# charger_v3.net
KiCad netlist of a schematic drawn in EAGLE
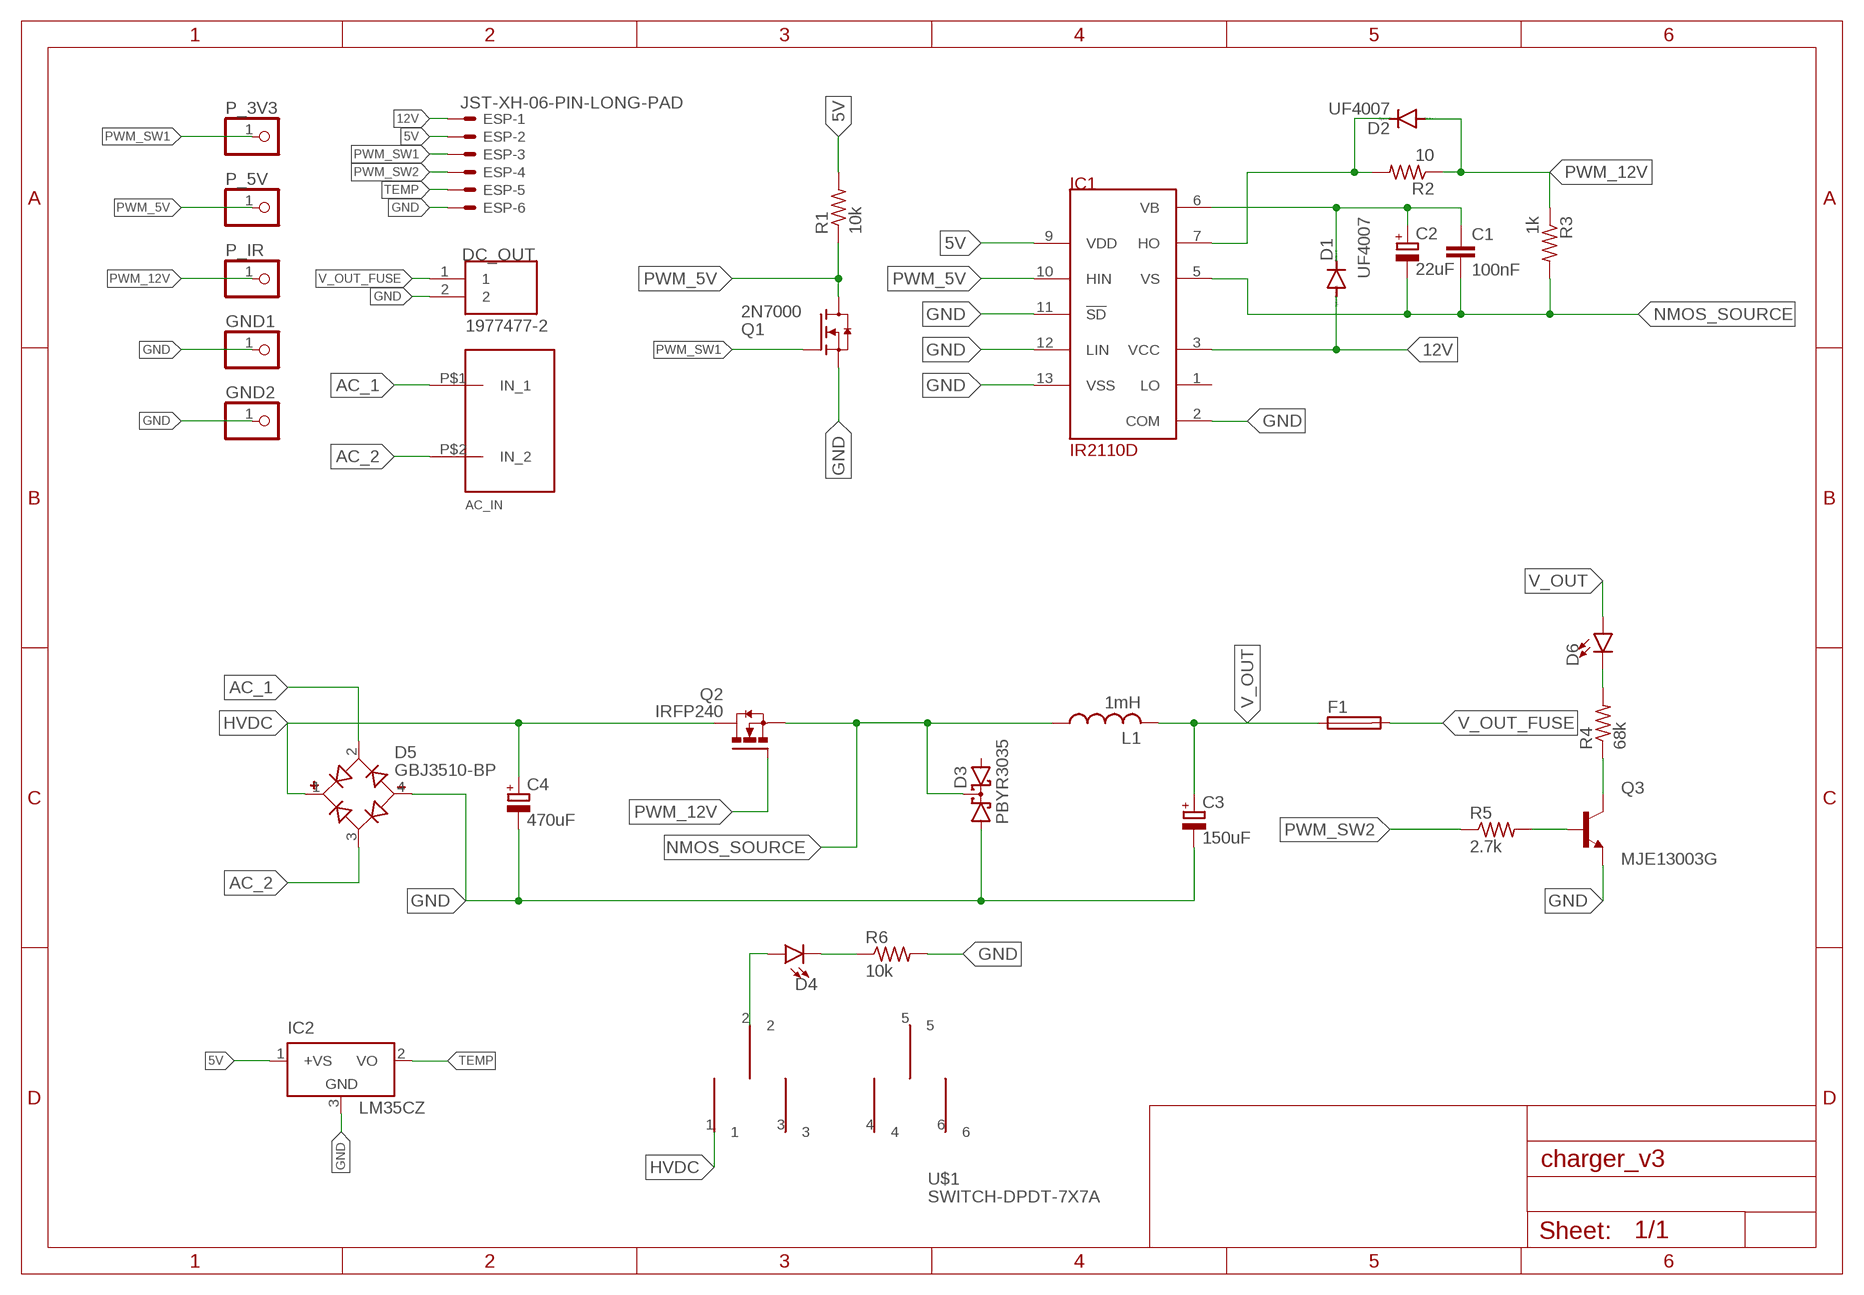
[diagram p0: schematic, sheet 1]

(export (version "E")
  (design (tool "Eeschema 10.0.6"))
  (components
    (comp (ref "AC_IN")
      (value "XT90A")
      (footprint "eagle-import:XT90-PAD")
      (libsource (lib "eagle-import") (part "XT90A"))
    )
    (comp (ref "C1")
      (value "100nF")
      (footprint "eagle-import:C025-025X050")
      (libsource (lib "eagle-import") (part "C-EU025-025X050"))
    )
    (comp (ref "C2")
      (value "22uF")
      (footprint "eagle-import:E2,5-6E")
      (libsource (lib "eagle-import") (part "CPOL-EUE2,5-6E"))
    )
    (comp (ref "C3")
      (value "150uF")
      (footprint "eagle-import:E7,5-18")
      (libsource (lib "eagle-import") (part "CPOL-EUE7.5-18"))
    )
    (comp (ref "C4")
      (value "470uF")
      (footprint "eagle-import:EB35D")
      (libsource (lib "eagle-import") (part "CPOL-EUE10-35"))
    )
    (comp (ref "D1")
      (value "UF4007")
      (footprint "eagle-import:DO34-7")
      (libsource (lib "eagle-import") (part "BAS15"))
    )
    (comp (ref "D2")
      (value "UF4007")
      (footprint "eagle-import:DO34-7")
      (libsource (lib "eagle-import") (part "BAS15"))
    )
    (comp (ref "D3")
      (value "PBYR3035")
      (footprint "eagle-import:SOT93S")
      (libsource (lib "eagle-import") (part "PBYR3035"))
    )
    (comp (ref "D4")
      (value "LED5MM")
      (footprint "eagle-import:LED_5MM")
      (libsource (lib "eagle-import") (part "LED5MM"))
    )
    (comp (ref "D5")
      (value "GBJ3510-BP")
      (footprint "eagle-import:DIOB_GBJ3510-BP")
      (fields (field (name "MF") "Micro Commercial"))
      (libsource (lib "eagle-import") (part "GBJ3510-BP"))
    )
    (comp (ref "D6")
      (value "LED5MM")
      (footprint "eagle-import:LED_5MM")
      (libsource (lib "eagle-import") (part "LED5MM"))
    )
    (comp (ref "DC_OUT")
      (value "1977477-2")
      (footprint "eagle-import:TE_1977477-2")
      (fields (field (name "MF") "TE Connectivity"))
      (libsource (lib "eagle-import") (part "1977477-2"))
    )
    (comp (ref "ESP")
      (value "JST-XH-06-PIN-LONG-PAD")
      (footprint "eagle-import:JST-XH-06-PACKAGE-LONG-PAD")
      (libsource (lib "eagle-import") (part "JST-XH-06-PIN-LONG-PAD"))
    )
    (comp (ref "F1")
      (value "SH25")
      (footprint "eagle-import:SH25")
      (fields (field (name "MF") "SCHURTER") (field (name "MPN") "0031.8211"))
      (libsource (lib "eagle-import") (part "SH25"))
    )
    (comp (ref "GND1")
      (value "PINHD-1X1")
      (footprint "eagle-import:1X01")
      (libsource (lib "eagle-import") (part "PINHD-1X1"))
    )
    (comp (ref "GND2")
      (value "PINHD-1X1")
      (footprint "eagle-import:1X01")
      (libsource (lib "eagle-import") (part "PINHD-1X1"))
    )
    (comp (ref "IC1")
      (value "IR2110D")
      (footprint "eagle-import:DIL14")
      (libsource (lib "eagle-import") (part "IR2110D"))
    )
    (comp (ref "IC2")
      (value "LM35CZ")
      (footprint "eagle-import:TO92")
      (libsource (lib "eagle-import") (part "LM35CZ"))
    )
    (comp (ref "L1")
      (value "1mH")
      (footprint "eagle-import:TJ7-U1")
      (libsource (lib "eagle-import") (part "L-USTJ7-U1"))
    )
    (comp (ref "P_3V3")
      (value "PINHD-1X1")
      (footprint "eagle-import:1X01")
      (libsource (lib "eagle-import") (part "PINHD-1X1"))
    )
    (comp (ref "P_5V")
      (value "PINHD-1X1")
      (footprint "eagle-import:1X01")
      (libsource (lib "eagle-import") (part "PINHD-1X1"))
    )
    (comp (ref "P_IR")
      (value "PINHD-1X1")
      (footprint "eagle-import:1X01")
      (libsource (lib "eagle-import") (part "PINHD-1X1"))
    )
    (comp (ref "Q1")
      (value "2N7000")
      (footprint "eagle-import:TO92")
      (fields (field (name "MF") "STMicroelectronics"))
      (libsource (lib "eagle-import") (part "2N7000"))
    )
    (comp (ref "Q2")
      (value "IRFP240")
      (footprint "eagle-import:TO247AC")
      (fields (field (name "MF") "Vishay Siliconix"))
      (libsource (lib "eagle-import") (part "IRFP240"))
    )
    (comp (ref "Q3")
      (value "MJE13003G")
      (footprint "eagle-import:TO229P780X300X1364-3")
      (fields (field (name "MF") "ON Semiconductor"))
      (libsource (lib "eagle-import") (part "MJE13003G"))
    )
    (comp (ref "R1")
      (value "10k")
      (footprint "eagle-import:0204_7")
      (libsource (lib "eagle-import") (part "R-US_0204/7"))
    )
    (comp (ref "R2")
      (value "10")
      (footprint "eagle-import:0204_7")
      (libsource (lib "eagle-import") (part "R-US_0204/7"))
    )
    (comp (ref "R3")
      (value "1k")
      (footprint "eagle-import:0204_7")
      (libsource (lib "eagle-import") (part "R-US_0204/7"))
    )
    (comp (ref "R4")
      (value "68k")
      (footprint "eagle-import:0309_12")
      (libsource (lib "eagle-import") (part "R-US_0309/12"))
    )
    (comp (ref "R5")
      (value "2.7k")
      (footprint "eagle-import:0204_7")
      (libsource (lib "eagle-import") (part "R-US_0204/7"))
    )
    (comp (ref "R6")
      (value "10k")
      (footprint "eagle-import:0204_7")
      (libsource (lib "eagle-import") (part "R-US_0204/7"))
    )
    (comp (ref "U$1")
      (value "SWITCH-DPDT-7X7A")
      (footprint "eagle-import:TL-2230")
      (libsource (lib "eagle-import") (part "SWITCH-DPDT-7X7A"))
    )
  )
  (nets
    (net (code "1") (name "5V") (class "Default")
      (node (ref "ESP") (pin "2") (pinfunction "S_2") (pintype "passive"))
      (node (ref "IC1") (pin "9") (pinfunction "VDD_9") (pintype "power_in"))
      (node (ref "IC2") (pin "1") (pinfunction "+VS_1") (pintype "input"))
      (node (ref "R1") (pin "2") (pinfunction "2_2") (pintype "passive"))
    )
    (net (code "2") (name "12V") (class "Default")
      (node (ref "D1") (pin "A") (pinfunction "A_A") (pintype "passive"))
      (node (ref "ESP") (pin "1") (pinfunction "S_1") (pintype "passive"))
      (node (ref "IC1") (pin "3") (pinfunction "VCC_3") (pintype "power_in"))
    )
    (net (code "3") (name "AC_1") (class "Default")
      (node (ref "AC_IN") (pin "P$1") (pinfunction "IN_1_P$1") (pintype "bidirectional"))
      (node (ref "D5") (pin "2") (pinfunction "AC1_2") (pintype "passive"))
    )
    (net (code "4") (name "AC_2") (class "Default")
      (node (ref "AC_IN") (pin "P$2") (pinfunction "IN_2_P$2") (pintype "bidirectional"))
      (node (ref "D5") (pin "3") (pinfunction "AC2_3") (pintype "passive"))
    )
    (net (code "5") (name "GND") (class "Default")
      (node (ref "C3") (pin "-") (pinfunction "-_-") (pintype "passive"))
      (node (ref "C4") (pin "-") (pinfunction "-_-") (pintype "passive"))
      (node (ref "D3") (pin "A1") (pinfunction "A1_A1") (pintype "passive"))
      (node (ref "D5") (pin "4") (pinfunction "-_4") (pintype "passive"))
      (node (ref "DC_OUT") (pin "2") (pinfunction "2_2") (pintype "passive"))
      (node (ref "ESP") (pin "6") (pinfunction "S_6") (pintype "passive"))
      (node (ref "GND1") (pin "1") (pinfunction "1_1") (pintype "passive"))
      (node (ref "GND2") (pin "1") (pinfunction "1_1") (pintype "passive"))
      (node (ref "IC1") (pin "11") (pinfunction "~{SD}_11") (pintype "input"))
      (node (ref "IC1") (pin "12") (pinfunction "LIN_12") (pintype "input"))
      (node (ref "IC1") (pin "13") (pinfunction "VSS_13") (pintype "power_in"))
      (node (ref "IC1") (pin "2") (pinfunction "COM_2") (pintype "power_in"))
      (node (ref "IC2") (pin "3") (pinfunction "GND_3") (pintype "power_in"))
      (node (ref "Q1") (pin "1") (pinfunction "S_1") (pintype "passive"))
      (node (ref "Q3") (pin "3") (pinfunction "E_3") (pintype "passive"))
      (node (ref "R6") (pin "2") (pinfunction "2_2") (pintype "passive"))
    )
    (net (code "6") (name "HVDC") (class "Default")
      (node (ref "C4") (pin "+") (pinfunction "+_+") (pintype "passive"))
      (node (ref "D5") (pin "1") (pinfunction "+_1") (pintype "passive"))
      (node (ref "Q2") (pin "2") (pinfunction "D_2") (pintype "passive"))
      (node (ref "U$1") (pin "1") (pinfunction "1_1") (pintype "bidirectional"))
    )
    (net (code "7") (name "NMOS_SOURCE") (class "Default")
      (node (ref "C1") (pin "2") (pinfunction "2_2") (pintype "passive"))
      (node (ref "C2") (pin "-") (pinfunction "-_-") (pintype "passive"))
      (node (ref "D3") (pin "C") (pinfunction "C_C") (pintype "passive"))
      (node (ref "IC1") (pin "5") (pinfunction "VS_5") (pintype "power_in"))
      (node (ref "L1") (pin "1") (pinfunction "1_1") (pintype "passive"))
      (node (ref "Q2") (pin "3") (pinfunction "S_3") (pintype "passive"))
      (node (ref "R3") (pin "2") (pinfunction "2_2") (pintype "passive"))
    )
    (net (code "8") (name "Net-(D4-C)") (class "Default")
      (node (ref "D4") (pin "K") (pinfunction "C_K") (pintype "passive"))
      (node (ref "R6") (pin "1") (pinfunction "1_1") (pintype "passive"))
    )
    (net (code "9") (name "Net-(D4-PadA)") (class "Default")
      (node (ref "D4") (pin "A") (pinfunction "A_A") (pintype "passive"))
      (node (ref "U$1") (pin "2") (pinfunction "2_2") (pintype "bidirectional"))
    )
    (net (code "10") (name "Net-(D6-C)") (class "Default")
      (node (ref "D6") (pin "K") (pinfunction "C_K") (pintype "passive"))
      (node (ref "R4") (pin "2") (pinfunction "2_2") (pintype "passive"))
    )
    (net (code "11") (name "Net-(IC1-HO)") (class "Default")
      (node (ref "D2") (pin "C") (pinfunction "C_C") (pintype "passive"))
      (node (ref "IC1") (pin "7") (pinfunction "HO_7") (pintype "output"))
      (node (ref "R2") (pin "2") (pinfunction "2_2") (pintype "passive"))
    )
    (net (code "12") (name "Net-(IC1-VB)") (class "Default")
      (node (ref "C1") (pin "1") (pinfunction "1_1") (pintype "passive"))
      (node (ref "C2") (pin "+") (pinfunction "+_+") (pintype "passive"))
      (node (ref "D1") (pin "C") (pinfunction "C_C") (pintype "passive"))
      (node (ref "IC1") (pin "6") (pinfunction "VB_6") (pintype "power_in"))
    )
    (net (code "13") (name "Net-(Q3-B)") (class "Default")
      (node (ref "Q3") (pin "1") (pinfunction "B_1") (pintype "passive"))
      (node (ref "R5") (pin "2") (pinfunction "2_2") (pintype "passive"))
    )
    (net (code "14") (name "Net-(Q3-C)") (class "Default")
      (node (ref "Q3") (pin "2") (pinfunction "C_2") (pintype "passive"))
      (node (ref "R4") (pin "1") (pinfunction "1_1") (pintype "passive"))
    )
    (net (code "15") (name "PWM_5V") (class "Default")
      (node (ref "IC1") (pin "10") (pinfunction "HIN_10") (pintype "input"))
      (node (ref "P_5V") (pin "1") (pinfunction "1_1") (pintype "passive"))
      (node (ref "Q1") (pin "3") (pinfunction "D_3") (pintype "passive"))
      (node (ref "R1") (pin "1") (pinfunction "1_1") (pintype "passive"))
    )
    (net (code "16") (name "PWM_12V") (class "Default")
      (node (ref "D2") (pin "A") (pinfunction "A_A") (pintype "passive"))
      (node (ref "P_IR") (pin "1") (pinfunction "1_1") (pintype "passive"))
      (node (ref "Q2") (pin "1") (pinfunction "G_1") (pintype "passive"))
      (node (ref "R2") (pin "1") (pinfunction "1_1") (pintype "passive"))
      (node (ref "R3") (pin "1") (pinfunction "1_1") (pintype "passive"))
    )
    (net (code "17") (name "PWM_SW1") (class "Default")
      (node (ref "ESP") (pin "3") (pinfunction "S_3") (pintype "passive"))
      (node (ref "P_3V3") (pin "1") (pinfunction "1_1") (pintype "passive"))
      (node (ref "Q1") (pin "2") (pinfunction "G_2") (pintype "passive"))
    )
    (net (code "18") (name "PWM_SW2") (class "Default")
      (node (ref "ESP") (pin "4") (pinfunction "S_4") (pintype "passive"))
      (node (ref "R5") (pin "1") (pinfunction "1_1") (pintype "passive"))
    )
    (net (code "19") (name "TEMP") (class "Default")
      (node (ref "ESP") (pin "5") (pinfunction "S_5") (pintype "passive"))
      (node (ref "IC2") (pin "2") (pinfunction "VO_2") (pintype "input"))
    )
    (net (code "20") (name "V_OUT") (class "Default")
      (node (ref "C3") (pin "+") (pinfunction "+_+") (pintype "passive"))
      (node (ref "D6") (pin "A") (pinfunction "A_A") (pintype "passive"))
      (node (ref "F1") (pin "1") (pinfunction "1_1") (pintype "passive"))
      (node (ref "L1") (pin "2") (pinfunction "2_2") (pintype "passive"))
    )
    (net (code "21") (name "V_OUT_FUSE") (class "Default")
      (node (ref "DC_OUT") (pin "1") (pinfunction "1_1") (pintype "passive"))
      (node (ref "F1") (pin "2") (pinfunction "2_2") (pintype "passive"))
    )
    (net (code "22") (name "unconnected-(D3-PadA2)") (class "Default")
      (node (ref "D3") (pin "A2") (pinfunction "A2_A2") (pintype "passive"))
    )
    (net (code "23") (name "unconnected-(IC1-LO-Pad1)") (class "Default")
      (node (ref "IC1") (pin "1") (pinfunction "LO_1") (pintype "output"))
    )
    (net (code "24") (name "unconnected-(U$1-Pad3)") (class "Default")
      (node (ref "U$1") (pin "3") (pinfunction "3_3") (pintype "bidirectional"))
    )
    (net (code "25") (name "unconnected-(U$1-Pad4)") (class "Default")
      (node (ref "U$1") (pin "4") (pinfunction "4_4") (pintype "bidirectional"))
    )
    (net (code "26") (name "unconnected-(U$1-Pad5)") (class "Default")
      (node (ref "U$1") (pin "5") (pinfunction "5_5") (pintype "bidirectional"))
    )
    (net (code "27") (name "unconnected-(U$1-Pad6)") (class "Default")
      (node (ref "U$1") (pin "6") (pinfunction "6_6") (pintype "bidirectional"))
    )
  )
)
